# EEM_connector.net
KiCad netlist of a schematic drawn in Altium Designer
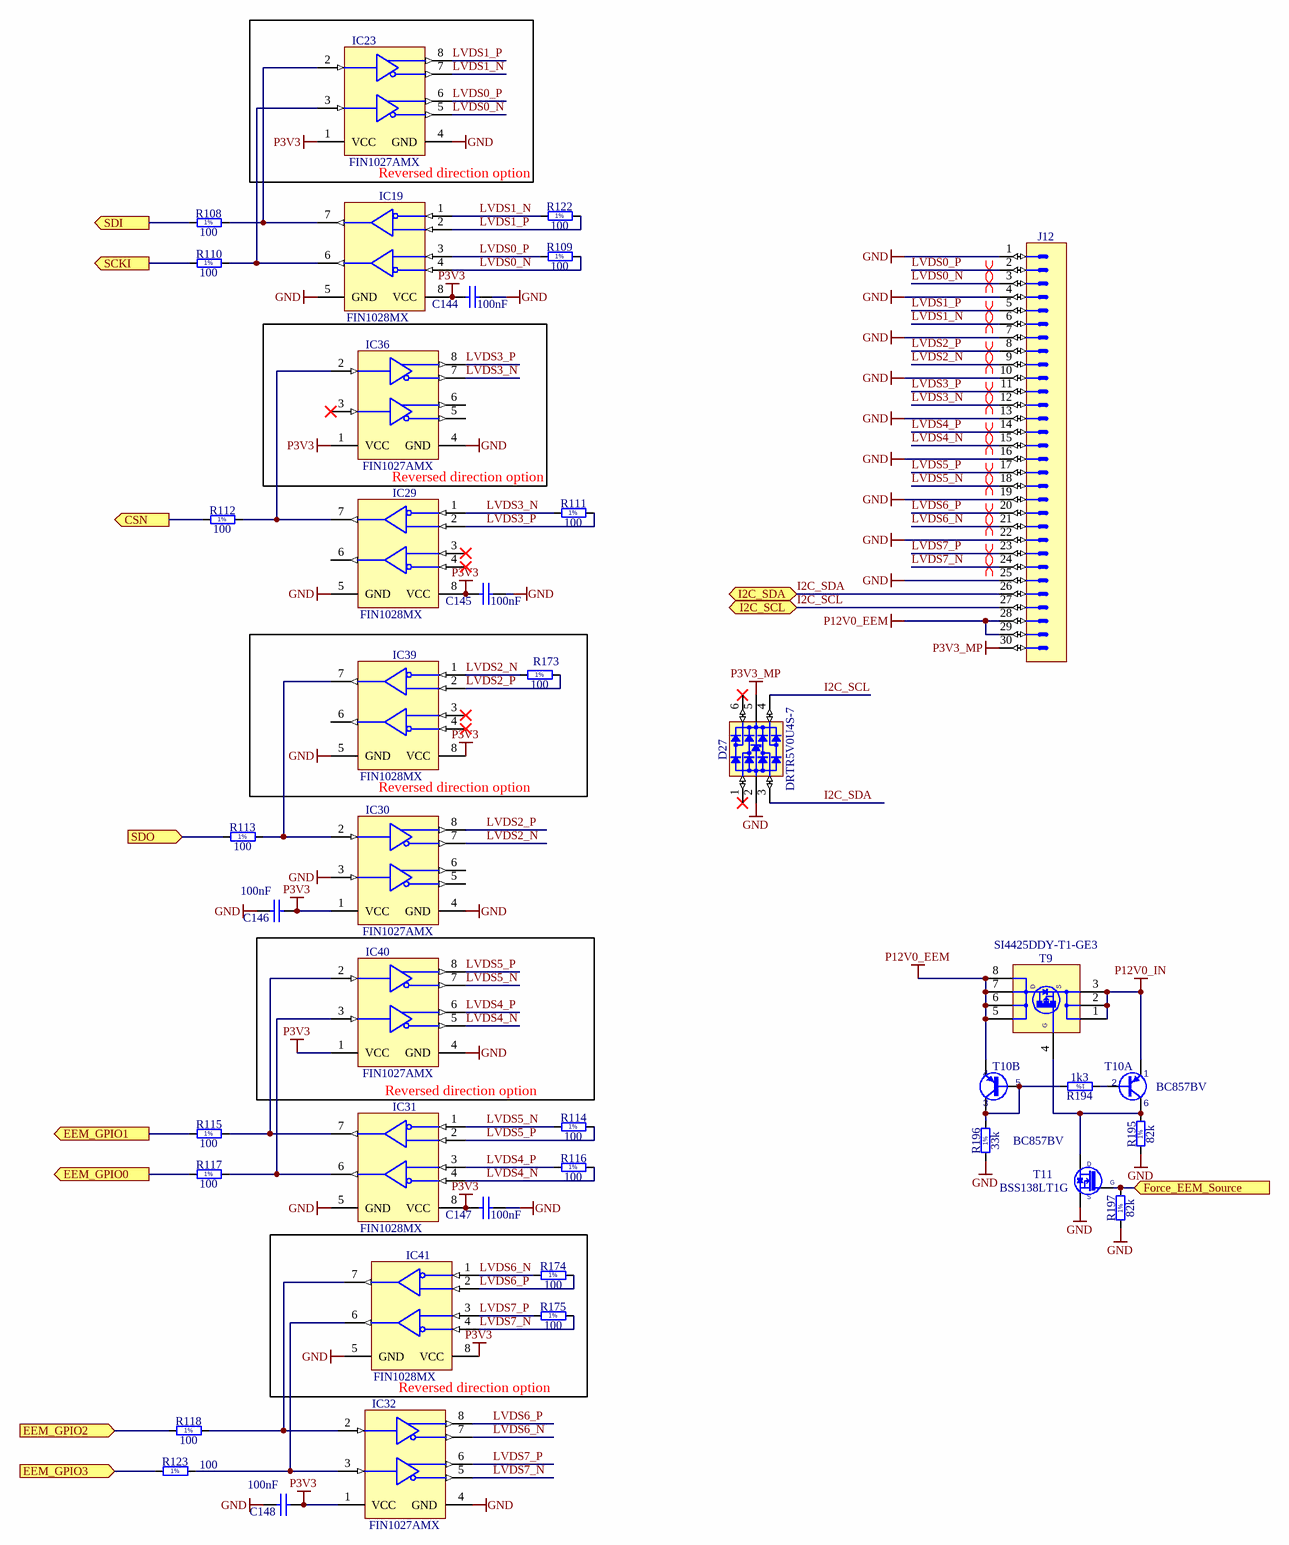
[diagram p0: EEM_connector.SchDoc]

(export (version "E")
  (design (tool "Eeschema 10.0.6"))
  (components
    (comp (ref "C144")
      (value "100nF")
      (footprint "CAPC1005X55N")
      (description "Non-polarised capacitor")
      (fields
        (field (name "PART NUMBER") "CC0402_100NF_16V_10%_X5R")
        (field (name "VOLTAGE") "16V")
        (field (name "AUTHOR") "CERN DEM JLC")
      )
      (libsource (lib "Capacitors") (part "Capacitor - non polarized"))
    )
    (comp (ref "C145")
      (value "100nF")
      (footprint "CAPC1005X55N")
      (description "Non-polarised capacitor")
      (fields
        (field (name "PART NUMBER") "CC0402_100NF_16V_10%_X5R")
        (field (name "VOLTAGE") "16V")
        (field (name "AUTHOR") "CERN DEM JLC")
      )
      (libsource (lib "Capacitors") (part "Capacitor - non polarized"))
    )
    (comp (ref "C146")
      (value "100nF")
      (footprint "CAPC1005X55N")
      (description "Non-polarised capacitor")
      (fields
        (field (name "PART NUMBER") "CC0402_100NF_16V_10%_X5R")
        (field (name "VOLTAGE") "16V")
        (field (name "AUTHOR") "CERN DEM JLC")
      )
      (libsource (lib "Capacitors") (part "Capacitor - non polarized"))
    )
    (comp (ref "C147")
      (value "100nF")
      (footprint "CAPC1005X55N")
      (description "Non-polarised capacitor")
      (fields
        (field (name "PART NUMBER") "CC0402_100NF_16V_10%_X5R")
        (field (name "VOLTAGE") "16V")
        (field (name "AUTHOR") "CERN DEM JLC")
      )
      (libsource (lib "Capacitors") (part "Capacitor - non polarized"))
    )
    (comp (ref "C148")
      (value "100nF")
      (footprint "CAPC1005X55N")
      (description "Non-polarised capacitor")
      (fields
        (field (name "PART NUMBER") "CC0402_100NF_16V_10%_X5R")
        (field (name "VOLTAGE") "16V")
        (field (name "AUTHOR") "CERN DEM JLC")
      )
      (libsource (lib "Capacitors") (part "Capacitor - non polarized"))
    )
    (comp (ref "D27")
      (value "DRTR5V0U4S-7")
      (footprint "SOT65P210X110-6N")
      (description "Integrated Quad Ultra-Low Capacitance ESD Protection")
      (fields (field (name "MANUFACTURER") "DIODES") (field (name "AUTHOR") "GK"))
      (libsource (lib "Diodes") (part "D_TVS_DRTR5V0U4S-7"))
    )
    (comp (ref "IC19")
      (value "FIN1028MX")
      (footprint "SOIC127P600X175-8N")
      (description "3.3V LVDS 2-Bit High-Speed Differential Reciever")
      (fields (field (name "MANUFACTURER") "ON Semiconductor") (field (name "AUTHOR") "GK"))
      (libsource (lib "LIBRARY_SCH") (part "IFC_FIN1028"))
    )
    (comp (ref "IC23")
      (value "FIN1027AMX")
      (footprint "SOIC127P600X175-8N")
      (description "3.3V LVDS, 2-Bit, High-Speed, Differential Driver")
      (fields (field (name "MANUFACTURER") "ON Semiconductor") (field (name "AUTHOR") "GK"))
      (libsource (lib "LIBRARY_SCH") (part "IFC_FIN1027A"))
    )
    (comp (ref "IC29")
      (value "FIN1028MX")
      (footprint "SOIC127P600X175-8N")
      (description "3.3V LVDS 2-Bit High-Speed Differential Reciever")
      (fields (field (name "MANUFACTURER") "ON Semiconductor") (field (name "AUTHOR") "GK"))
      (libsource (lib "LIBRARY_SCH") (part "IFC_FIN1028"))
    )
    (comp (ref "IC30")
      (value "FIN1027AMX")
      (footprint "SOIC127P600X175-8N")
      (description "3.3V LVDS, 2-Bit, High-Speed, Differential Driver")
      (fields (field (name "MANUFACTURER") "ON Semiconductor") (field (name "AUTHOR") "GK"))
      (libsource (lib "LIBRARY_SCH") (part "IFC_FIN1027A"))
    )
    (comp (ref "IC31")
      (value "FIN1028MX")
      (footprint "SOIC127P600X175-8N")
      (description "3.3V LVDS 2-Bit High-Speed Differential Reciever")
      (fields (field (name "MANUFACTURER") "ON Semiconductor") (field (name "AUTHOR") "GK"))
      (libsource (lib "LIBRARY_SCH") (part "IFC_FIN1028"))
    )
    (comp (ref "IC32")
      (value "FIN1027AMX")
      (footprint "SOIC127P600X175-8N")
      (description "3.3V LVDS, 2-Bit, High-Speed, Differential Driver")
      (fields (field (name "MANUFACTURER") "ON Semiconductor") (field (name "AUTHOR") "GK"))
      (libsource (lib "LIBRARY_SCH") (part "IFC_FIN1027A"))
    )
    (comp (ref "IC36")
      (value "FIN1027AMX")
      (footprint "SOIC127P600X175-8N")
      (description "3.3V LVDS, 2-Bit, High-Speed, Differential Driver")
      (fields (field (name "MANUFACTURER") "ON Semiconductor") (field (name "AUTHOR") "GK"))
      (libsource (lib "LIBRARY_SCH") (part "IFC_FIN1027A"))
    )
    (comp (ref "IC39")
      (value "FIN1028MX")
      (footprint "SOIC127P600X175-8N")
      (description "3.3V LVDS 2-Bit High-Speed Differential Reciever")
      (fields (field (name "MANUFACTURER") "ON Semiconductor") (field (name "AUTHOR") "GK"))
      (libsource (lib "LIBRARY_SCH") (part "IFC_FIN1028"))
    )
    (comp (ref "IC40")
      (value "FIN1027AMX")
      (footprint "SOIC127P600X175-8N")
      (description "3.3V LVDS, 2-Bit, High-Speed, Differential Driver")
      (fields (field (name "MANUFACTURER") "ON Semiconductor") (field (name "AUTHOR") "GK"))
      (libsource (lib "LIBRARY_SCH") (part "IFC_FIN1027A"))
    )
    (comp (ref "IC41")
      (value "FIN1028MX")
      (footprint "SOIC127P600X175-8N")
      (description "3.3V LVDS 2-Bit High-Speed Differential Reciever")
      (fields (field (name "MANUFACTURER") "ON Semiconductor") (field (name "AUTHOR") "GK"))
      (libsource (lib "LIBRARY_SCH") (part "IFC_FIN1028"))
    )
    (comp (ref "J12")
      (value "~")
      (footprint "3M_N2530-6002RB")
      (description "Connector 30 Male")
      (fields
        (field (name "PART NUMBER") "3M_N2530-6002RB")
        (field (name "MANUFACTURER") "3M")
        (field (name "AUTHOR") "CERN DEM JLC")
      )
      (libsource (lib "Connectors") (part "Connector 30 Male"))
    )
    (comp (ref "R108")
      (value "100")
      (footprint "RESC1005X40N")
      (description "Resistor - 1%")
      (fields
        (field (name "PART NUMBER") "R0402_100R_1%_0.0625W_100PPM")
        (field (name "POWER") "0.0625W")
        (field (name "AUTHOR") "CERN DEM JLC")
      )
      (libsource (lib "Resistors") (part "Resistor - 1%"))
    )
    (comp (ref "R109")
      (value "100")
      (footprint "RESC1005X40N")
      (description "Resistor - 1%")
      (fields
        (field (name "PART NUMBER") "R0402_100R_1%_0.0625W_100PPM")
        (field (name "POWER") "0.0625W")
        (field (name "AUTHOR") "CERN DEM JLC")
      )
      (libsource (lib "Resistors") (part "Resistor - 1%"))
    )
    (comp (ref "R110")
      (value "100")
      (footprint "RESC1005X40N")
      (description "Resistor - 1%")
      (fields
        (field (name "PART NUMBER") "R0402_100R_1%_0.0625W_100PPM")
        (field (name "POWER") "0.0625W")
        (field (name "AUTHOR") "CERN DEM JLC")
      )
      (libsource (lib "Resistors") (part "Resistor - 1%"))
    )
    (comp (ref "R111")
      (value "100")
      (footprint "RESC1005X40N")
      (description "Resistor - 1%")
      (fields
        (field (name "PART NUMBER") "R0402_100R_1%_0.0625W_100PPM")
        (field (name "POWER") "0.0625W")
        (field (name "AUTHOR") "CERN DEM JLC")
      )
      (libsource (lib "Resistors") (part "Resistor - 1%"))
    )
    (comp (ref "R112")
      (value "100")
      (footprint "RESC1005X40N")
      (description "Resistor - 1%")
      (fields
        (field (name "PART NUMBER") "R0402_100R_1%_0.0625W_100PPM")
        (field (name "POWER") "0.0625W")
        (field (name "AUTHOR") "CERN DEM JLC")
      )
      (libsource (lib "Resistors") (part "Resistor - 1%"))
    )
    (comp (ref "R113")
      (value "100")
      (footprint "RESC1005X40N")
      (description "Resistor - 1%")
      (fields
        (field (name "PART NUMBER") "R0402_100R_1%_0.0625W_100PPM")
        (field (name "POWER") "0.0625W")
        (field (name "AUTHOR") "CERN DEM JLC")
      )
      (libsource (lib "Resistors") (part "Resistor - 1%"))
    )
    (comp (ref "R114")
      (value "100")
      (footprint "RESC1005X40N")
      (description "Resistor - 1%")
      (fields
        (field (name "PART NUMBER") "R0402_100R_1%_0.0625W_100PPM")
        (field (name "POWER") "0.0625W")
        (field (name "AUTHOR") "CERN DEM JLC")
      )
      (libsource (lib "Resistors") (part "Resistor - 1%"))
    )
    (comp (ref "R115")
      (value "100")
      (footprint "RESC1005X40N")
      (description "Resistor - 1%")
      (fields
        (field (name "PART NUMBER") "R0402_100R_1%_0.0625W_100PPM")
        (field (name "POWER") "0.0625W")
        (field (name "AUTHOR") "CERN DEM JLC")
      )
      (libsource (lib "Resistors") (part "Resistor - 1%"))
    )
    (comp (ref "R116")
      (value "100")
      (footprint "RESC1005X40N")
      (description "Resistor - 1%")
      (fields
        (field (name "PART NUMBER") "R0402_100R_1%_0.0625W_100PPM")
        (field (name "POWER") "0.0625W")
        (field (name "AUTHOR") "CERN DEM JLC")
      )
      (libsource (lib "Resistors") (part "Resistor - 1%"))
    )
    (comp (ref "R117")
      (value "100")
      (footprint "RESC1005X40N")
      (description "Resistor - 1%")
      (fields
        (field (name "PART NUMBER") "R0402_100R_1%_0.0625W_100PPM")
        (field (name "POWER") "0.0625W")
        (field (name "AUTHOR") "CERN DEM JLC")
      )
      (libsource (lib "Resistors") (part "Resistor - 1%"))
    )
    (comp (ref "R118")
      (value "100")
      (footprint "RESC1005X40N")
      (description "Resistor - 1%")
      (fields
        (field (name "PART NUMBER") "R0402_100R_1%_0.0625W_100PPM")
        (field (name "POWER") "0.0625W")
        (field (name "AUTHOR") "CERN DEM JLC")
      )
      (libsource (lib "Resistors") (part "Resistor - 1%"))
    )
    (comp (ref "R122")
      (value "100")
      (footprint "RESC1005X40N")
      (description "Resistor - 1%")
      (fields
        (field (name "PART NUMBER") "R0402_100R_1%_0.0625W_100PPM")
        (field (name "POWER") "0.0625W")
        (field (name "AUTHOR") "CERN DEM JLC")
      )
      (libsource (lib "Resistors") (part "Resistor - 1%"))
    )
    (comp (ref "R123")
      (value "100")
      (footprint "RESC1005X40N")
      (description "Resistor - 1%")
      (fields
        (field (name "PART NUMBER") "R0402_100R_1%_0.0625W_100PPM")
        (field (name "POWER") "0.0625W")
        (field (name "AUTHOR") "CERN DEM JLC")
      )
      (libsource (lib "Resistors") (part "Resistor - 1%"))
    )
    (comp (ref "R173")
      (value "100")
      (footprint "RESC1005X40N")
      (description "Resistor - 1%")
      (fields
        (field (name "PART NUMBER") "R0402_100R_1%_0.0625W_100PPM")
        (field (name "POWER") "0.0625W")
        (field (name "AUTHOR") "CERN DEM JLC")
      )
      (libsource (lib "Resistors") (part "Resistor - 1%"))
    )
    (comp (ref "R174")
      (value "100")
      (footprint "RESC1005X40N")
      (description "Resistor - 1%")
      (fields
        (field (name "PART NUMBER") "R0402_100R_1%_0.0625W_100PPM")
        (field (name "POWER") "0.0625W")
        (field (name "AUTHOR") "CERN DEM JLC")
      )
      (libsource (lib "Resistors") (part "Resistor - 1%"))
    )
    (comp (ref "R175")
      (value "100")
      (footprint "RESC1005X40N")
      (description "Resistor - 1%")
      (fields
        (field (name "PART NUMBER") "R0402_100R_1%_0.0625W_100PPM")
        (field (name "POWER") "0.0625W")
        (field (name "AUTHOR") "CERN DEM JLC")
      )
      (libsource (lib "Resistors") (part "Resistor - 1%"))
    )
    (comp (ref "R194")
      (value "1k3")
      (footprint "RESC1608X55N")
      (description "Resistor - 1%")
      (fields
        (field (name "PART NUMBER") "R0603_1K3_1%_0.1W_100PPM")
        (field (name "POWER") "0.1W")
        (field (name "AUTHOR") "CERN DEM JLC")
      )
      (libsource (lib "Resistors") (part "Resistor - 1%"))
    )
    (comp (ref "R195")
      (value "82k")
      (footprint "RESC1608X55N")
      (description "Resistor - 1%")
      (fields
        (field (name "PART NUMBER") "R0603_82K_1%_0.1W_100PPM")
        (field (name "POWER") "0.1W")
        (field (name "AUTHOR") "CERN DEM JLC")
      )
      (libsource (lib "Resistors") (part "Resistor - 1%"))
    )
    (comp (ref "R196")
      (value "33k")
      (footprint "RESC1005X40N")
      (description "Resistor - 1%")
      (fields
        (field (name "PART NUMBER") "R0402_33K_1%_0.0625W_100PPM")
        (field (name "POWER") "0.0625W")
        (field (name "AUTHOR") "CERN DEM JLC")
      )
      (libsource (lib "Resistors") (part "Resistor - 1%"))
    )
    (comp (ref "R197")
      (value "82k")
      (footprint "RESC1608X55N")
      (description "Resistor - 1%")
      (fields
        (field (name "PART NUMBER") "R0603_82K_1%_0.1W_100PPM")
        (field (name "POWER") "0.1W")
        (field (name "AUTHOR") "CERN DEM JLC")
      )
      (libsource (lib "Resistors") (part "Resistor - 1%"))
    )
    (comp (ref "T9")
      (value "SI4425DDY-T1-GE3")
      (footprint "SOIC127P600X175-8N")
      (description "-30V -19.7A P-Channel MOSFET")
      (fields (field (name "MANUFACTURER") "VISHAY SILICONIX") (field (name "AUTHOR") "CERN DEM MR"))
      (libsource (lib "ICs And Semiconductors") (part "SI4425DDY"))
    )
    (comp (ref "T10")
      (value "BC857BV")
      (footprint "SOTFL50P160X60-6N")
      (description "45V, 100mA PNP General Purpose Double Transistor")
      (fields (field (name "MANUFACTURER") "NXP SEMICONDUCTORS") (field (name "AUTHOR") "CERN DEM JLC"))
      (libsource (lib "") (part "BC857BV_1"))
    )
    (comp (ref "T11")
      (value "BSS138LT1G")
      (footprint "SOT95P240X110-3N")
      (description "N-CHANNEL MOSFET WITH DIODE")
      (fields (field (name "MANUFACTURER") "ON SEMICONDUCTOR") (field (name "AUTHOR") "CERN DEM JLC"))
      (libsource (lib "ICs And Semiconductors") (part "N-MOSFET-D 1G 2S 3D"))
    )
  )
  (nets
    (net (code "1") (name "/CSN") (class "Default")
      (node (ref "R112") (pin "1") (pinfunction "1_1") (pintype "passive"))
    )
    (net (code "2") (name "/EEM_GPIO0") (class "Default")
      (node (ref "R117") (pin "1") (pinfunction "1_1") (pintype "passive"))
    )
    (net (code "3") (name "/EEM_GPIO1") (class "Default")
      (node (ref "R115") (pin "1") (pinfunction "1_1") (pintype "passive"))
    )
    (net (code "4") (name "/EEM_GPIO2") (class "Default")
      (node (ref "R118") (pin "1") (pinfunction "1_1") (pintype "passive"))
    )
    (net (code "5") (name "/EEM_GPIO3") (class "Default")
      (node (ref "R123") (pin "1") (pinfunction "1_1") (pintype "passive"))
    )
    (net (code "6") (name "/Force_EEM_Source") (class "Default")
      (node (ref "R197") (pin "2") (pinfunction "2_2") (pintype "passive"))
      (node (ref "T11") (pin "1") (pinfunction "G_1") (pintype "passive"))
    )
    (net (code "7") (name "/I2C_SCL") (class "Default")
      (node (ref "D27") (pin "4") (pinfunction "I/O3_4") (pintype "bidirectional"))
      (node (ref "J12") (pin "27") (pinfunction "27_27") (pintype "bidirectional"))
    )
    (net (code "8") (name "/I2C_SDA") (class "Default")
      (node (ref "D27") (pin "3") (pinfunction "I/O2_3") (pintype "bidirectional"))
      (node (ref "J12") (pin "26") (pinfunction "26_26") (pintype "bidirectional"))
    )
    (net (code "9") (name "/LVDS0_N") (class "Default")
      (node (ref "IC19") (pin "4") (pinfunction "RIN2-_4") (pintype "input"))
      (node (ref "IC23") (pin "5") (pinfunction "DOUT-_5") (pintype "output"))
      (node (ref "J12") (pin "3") (pinfunction "3_3") (pintype "bidirectional"))
      (node (ref "R109") (pin "2") (pinfunction "2_2") (pintype "passive"))
    )
    (net (code "10") (name "/LVDS0_P") (class "Default")
      (node (ref "IC19") (pin "3") (pinfunction "RIN2+_3") (pintype "input"))
      (node (ref "IC23") (pin "6") (pinfunction "DOUT+_6") (pintype "output"))
      (node (ref "J12") (pin "2") (pinfunction "2_2") (pintype "bidirectional"))
      (node (ref "R109") (pin "1") (pinfunction "1_1") (pintype "passive"))
    )
    (net (code "11") (name "/LVDS1_N") (class "Default")
      (node (ref "IC19") (pin "1") (pinfunction "RIN1-_1") (pintype "input"))
      (node (ref "IC23") (pin "7") (pinfunction "DOUT-_7") (pintype "output"))
      (node (ref "J12") (pin "6") (pinfunction "6_6") (pintype "bidirectional"))
      (node (ref "R122") (pin "1") (pinfunction "1_1") (pintype "passive"))
    )
    (net (code "12") (name "/LVDS1_P") (class "Default")
      (node (ref "IC19") (pin "2") (pinfunction "RIN1+_2") (pintype "input"))
      (node (ref "IC23") (pin "8") (pinfunction "DOUT+_8") (pintype "output"))
      (node (ref "J12") (pin "5") (pinfunction "5_5") (pintype "bidirectional"))
      (node (ref "R122") (pin "2") (pinfunction "2_2") (pintype "passive"))
    )
    (net (code "13") (name "/LVDS2_N") (class "Default")
      (node (ref "IC30") (pin "7") (pinfunction "DOUT-_7") (pintype "output"))
      (node (ref "IC39") (pin "1") (pinfunction "RIN1-_1") (pintype "input"))
      (node (ref "J12") (pin "9") (pinfunction "9_9") (pintype "bidirectional"))
      (node (ref "R173") (pin "1") (pinfunction "1_1") (pintype "passive"))
    )
    (net (code "14") (name "/LVDS2_P") (class "Default")
      (node (ref "IC30") (pin "8") (pinfunction "DOUT+_8") (pintype "output"))
      (node (ref "IC39") (pin "2") (pinfunction "RIN1+_2") (pintype "input"))
      (node (ref "J12") (pin "8") (pinfunction "8_8") (pintype "bidirectional"))
      (node (ref "R173") (pin "2") (pinfunction "2_2") (pintype "passive"))
    )
    (net (code "15") (name "/LVDS3_N") (class "Default")
      (node (ref "IC29") (pin "1") (pinfunction "RIN1-_1") (pintype "input"))
      (node (ref "IC36") (pin "7") (pinfunction "DOUT-_7") (pintype "output"))
      (node (ref "J12") (pin "12") (pinfunction "12_12") (pintype "bidirectional"))
      (node (ref "R111") (pin "1") (pinfunction "1_1") (pintype "passive"))
    )
    (net (code "16") (name "/LVDS3_P") (class "Default")
      (node (ref "IC29") (pin "2") (pinfunction "RIN1+_2") (pintype "input"))
      (node (ref "IC36") (pin "8") (pinfunction "DOUT+_8") (pintype "output"))
      (node (ref "J12") (pin "11") (pinfunction "11_11") (pintype "bidirectional"))
      (node (ref "R111") (pin "2") (pinfunction "2_2") (pintype "passive"))
    )
    (net (code "17") (name "/LVDS4_N") (class "Default")
      (node (ref "IC31") (pin "4") (pinfunction "RIN2-_4") (pintype "input"))
      (node (ref "IC40") (pin "5") (pinfunction "DOUT-_5") (pintype "output"))
      (node (ref "J12") (pin "15") (pinfunction "15_15") (pintype "bidirectional"))
      (node (ref "R116") (pin "2") (pinfunction "2_2") (pintype "passive"))
    )
    (net (code "18") (name "/LVDS4_P") (class "Default")
      (node (ref "IC31") (pin "3") (pinfunction "RIN2+_3") (pintype "input"))
      (node (ref "IC40") (pin "6") (pinfunction "DOUT+_6") (pintype "output"))
      (node (ref "J12") (pin "14") (pinfunction "14_14") (pintype "bidirectional"))
      (node (ref "R116") (pin "1") (pinfunction "1_1") (pintype "passive"))
    )
    (net (code "19") (name "/LVDS5_N") (class "Default")
      (node (ref "IC31") (pin "1") (pinfunction "RIN1-_1") (pintype "input"))
      (node (ref "IC40") (pin "7") (pinfunction "DOUT-_7") (pintype "output"))
      (node (ref "J12") (pin "18") (pinfunction "18_18") (pintype "bidirectional"))
      (node (ref "R114") (pin "1") (pinfunction "1_1") (pintype "passive"))
    )
    (net (code "20") (name "/LVDS5_P") (class "Default")
      (node (ref "IC31") (pin "2") (pinfunction "RIN1+_2") (pintype "input"))
      (node (ref "IC40") (pin "8") (pinfunction "DOUT+_8") (pintype "output"))
      (node (ref "J12") (pin "17") (pinfunction "17_17") (pintype "bidirectional"))
      (node (ref "R114") (pin "2") (pinfunction "2_2") (pintype "passive"))
    )
    (net (code "21") (name "/LVDS6_N") (class "Default")
      (node (ref "IC32") (pin "7") (pinfunction "DOUT-_7") (pintype "output"))
      (node (ref "IC41") (pin "1") (pinfunction "RIN1-_1") (pintype "input"))
      (node (ref "J12") (pin "21") (pinfunction "21_21") (pintype "bidirectional"))
      (node (ref "R174") (pin "1") (pinfunction "1_1") (pintype "passive"))
    )
    (net (code "22") (name "/LVDS6_P") (class "Default")
      (node (ref "IC32") (pin "8") (pinfunction "DOUT+_8") (pintype "output"))
      (node (ref "IC41") (pin "2") (pinfunction "RIN1+_2") (pintype "input"))
      (node (ref "J12") (pin "20") (pinfunction "20_20") (pintype "bidirectional"))
      (node (ref "R174") (pin "2") (pinfunction "2_2") (pintype "passive"))
    )
    (net (code "23") (name "/LVDS7_N") (class "Default")
      (node (ref "IC32") (pin "5") (pinfunction "DOUT-_5") (pintype "output"))
      (node (ref "IC41") (pin "4") (pinfunction "RIN2-_4") (pintype "input"))
      (node (ref "J12") (pin "24") (pinfunction "24_24") (pintype "bidirectional"))
      (node (ref "R175") (pin "2") (pinfunction "2_2") (pintype "passive"))
    )
    (net (code "24") (name "/LVDS7_P") (class "Default")
      (node (ref "IC32") (pin "6") (pinfunction "DOUT+_6") (pintype "output"))
      (node (ref "IC41") (pin "3") (pinfunction "RIN2+_3") (pintype "input"))
      (node (ref "J12") (pin "23") (pinfunction "23_23") (pintype "bidirectional"))
      (node (ref "R175") (pin "1") (pinfunction "1_1") (pintype "passive"))
    )
    (net (code "25") (name "/SCKI") (class "Default")
      (node (ref "R110") (pin "1") (pinfunction "1_1") (pintype "passive"))
    )
    (net (code "26") (name "/SDI") (class "Default")
      (node (ref "R108") (pin "1") (pinfunction "1_1") (pintype "passive"))
    )
    (net (code "27") (name "/SDO") (class "Default")
      (node (ref "R113") (pin "1") (pinfunction "1_1") (pintype "passive"))
    )
    (net (code "28") (name "GND") (class "Default")
      (node (ref "C144") (pin "1") (pinfunction "1_1") (pintype "passive"))
      (node (ref "C145") (pin "1") (pinfunction "1_1") (pintype "passive"))
      (node (ref "C146") (pin "1") (pinfunction "1_1") (pintype "passive"))
      (node (ref "C147") (pin "1") (pinfunction "1_1") (pintype "passive"))
      (node (ref "C148") (pin "1") (pinfunction "1_1") (pintype "passive"))
      (node (ref "D27") (pin "2") (pinfunction "GND_2") (pintype "power_in"))
      (node (ref "IC19") (pin "5") (pinfunction "GND_5") (pintype "power_in"))
      (node (ref "IC23") (pin "4") (pinfunction "GND_4") (pintype "power_in"))
      (node (ref "IC29") (pin "5") (pinfunction "GND_5") (pintype "power_in"))
      (node (ref "IC30") (pin "3") (pinfunction "DIN2RIN-_3") (pintype "input"))
      (node (ref "IC30") (pin "4") (pinfunction "GND_4") (pintype "power_in"))
      (node (ref "IC31") (pin "5") (pinfunction "GND_5") (pintype "power_in"))
      (node (ref "IC32") (pin "4") (pinfunction "GND_4") (pintype "power_in"))
      (node (ref "IC36") (pin "4") (pinfunction "GND_4") (pintype "power_in"))
      (node (ref "IC39") (pin "5") (pinfunction "GND_5") (pintype "power_in"))
      (node (ref "IC40") (pin "4") (pinfunction "GND_4") (pintype "power_in"))
      (node (ref "IC41") (pin "5") (pinfunction "GND_5") (pintype "power_in"))
      (node (ref "J12") (pin "1") (pinfunction "1_1") (pintype "bidirectional"))
      (node (ref "J12") (pin "10") (pinfunction "10_10") (pintype "bidirectional"))
      (node (ref "J12") (pin "13") (pinfunction "13_13") (pintype "bidirectional"))
      (node (ref "J12") (pin "16") (pinfunction "16_16") (pintype "bidirectional"))
      (node (ref "J12") (pin "19") (pinfunction "19_19") (pintype "bidirectional"))
      (node (ref "J12") (pin "22") (pinfunction "22_22") (pintype "bidirectional"))
      (node (ref "J12") (pin "25") (pinfunction "25_25") (pintype "bidirectional"))
      (node (ref "J12") (pin "4") (pinfunction "4_4") (pintype "bidirectional"))
      (node (ref "J12") (pin "7") (pinfunction "7_7") (pintype "bidirectional"))
      (node (ref "R195") (pin "1") (pinfunction "1_1") (pintype "passive"))
      (node (ref "R196") (pin "1") (pinfunction "1_1") (pintype "passive"))
      (node (ref "R197") (pin "1") (pinfunction "1_1") (pintype "passive"))
      (node (ref "T11") (pin "2") (pinfunction "S_2") (pintype "passive"))
    )
    (net (code "29") (name "Net-(IC19-ROUT1)") (class "Default")
      (node (ref "IC19") (pin "7") (pinfunction "ROUT1_7") (pintype "output"))
      (node (ref "IC23") (pin "2") (pinfunction "DIN1_2") (pintype "input"))
      (node (ref "R108") (pin "2") (pinfunction "2_2") (pintype "passive"))
    )
    (net (code "30") (name "Net-(IC19-ROUT2)") (class "Default")
      (node (ref "IC19") (pin "6") (pinfunction "ROUT2_6") (pintype "output"))
      (node (ref "IC23") (pin "3") (pinfunction "DIN2RIN-_3") (pintype "input"))
      (node (ref "R110") (pin "2") (pinfunction "2_2") (pintype "passive"))
    )
    (net (code "31") (name "Net-(IC29-ROUT1)") (class "Default")
      (node (ref "IC29") (pin "7") (pinfunction "ROUT1_7") (pintype "output"))
      (node (ref "IC36") (pin "2") (pinfunction "DIN1_2") (pintype "input"))
      (node (ref "R112") (pin "2") (pinfunction "2_2") (pintype "passive"))
    )
    (net (code "32") (name "Net-(IC30-DIN1)") (class "Default")
      (node (ref "IC30") (pin "2") (pinfunction "DIN1_2") (pintype "input"))
      (node (ref "IC39") (pin "7") (pinfunction "ROUT1_7") (pintype "output"))
      (node (ref "R113") (pin "2") (pinfunction "2_2") (pintype "passive"))
    )
    (net (code "33") (name "Net-(IC31-ROUT1)") (class "Default")
      (node (ref "IC31") (pin "7") (pinfunction "ROUT1_7") (pintype "output"))
      (node (ref "IC40") (pin "2") (pinfunction "DIN1_2") (pintype "input"))
      (node (ref "R115") (pin "2") (pinfunction "2_2") (pintype "passive"))
    )
    (net (code "34") (name "Net-(IC31-ROUT2)") (class "Default")
      (node (ref "IC31") (pin "6") (pinfunction "ROUT2_6") (pintype "output"))
      (node (ref "IC40") (pin "3") (pinfunction "DIN2RIN-_3") (pintype "input"))
      (node (ref "R117") (pin "2") (pinfunction "2_2") (pintype "passive"))
    )
    (net (code "35") (name "Net-(IC32-DIN1)") (class "Default")
      (node (ref "IC32") (pin "2") (pinfunction "DIN1_2") (pintype "input"))
      (node (ref "IC41") (pin "7") (pinfunction "ROUT1_7") (pintype "output"))
      (node (ref "R118") (pin "2") (pinfunction "2_2") (pintype "passive"))
    )
    (net (code "36") (name "Net-(IC32-DIN2RIN-)") (class "Default")
      (node (ref "IC32") (pin "3") (pinfunction "DIN2RIN-_3") (pintype "input"))
      (node (ref "IC41") (pin "6") (pinfunction "ROUT2_6") (pintype "output"))
      (node (ref "R123") (pin "2") (pinfunction "2_2") (pintype "passive"))
    )
    (net (code "37") (name "Net-(T10A-B)") (class "Default")
      (node (ref "R194") (pin "1") (pinfunction "1_1") (pintype "passive"))
      (node (ref "T10") (pin "2") (pinfunction "B_2") (pintype "passive"))
    )
    (net (code "38") (name "Net-(T10A-C)") (class "Default")
      (node (ref "R195") (pin "2") (pinfunction "2_2") (pintype "passive"))
      (node (ref "T10") (pin "6") (pinfunction "C_6") (pintype "passive"))
      (node (ref "T11") (pin "3") (pinfunction "D_3") (pintype "passive"))
      (node (ref "T9") (pin "4") (pinfunction "S_4") (pintype "passive"))
    )
    (net (code "39") (name "Net-(T10B-B)") (class "Default")
      (node (ref "R194") (pin "2") (pinfunction "2_2") (pintype "passive"))
      (node (ref "R196") (pin "2") (pinfunction "2_2") (pintype "passive"))
      (node (ref "T10") (pin "3") (pinfunction "C_3") (pintype "passive"))
      (node (ref "T10") (pin "5") (pinfunction "B_5") (pintype "passive"))
    )
    (net (code "40") (name "P3V3") (class "Default")
      (node (ref "C144") (pin "2") (pinfunction "2_2") (pintype "passive"))
      (node (ref "C145") (pin "2") (pinfunction "2_2") (pintype "passive"))
      (node (ref "C146") (pin "2") (pinfunction "2_2") (pintype "passive"))
      (node (ref "C147") (pin "2") (pinfunction "2_2") (pintype "passive"))
      (node (ref "C148") (pin "2") (pinfunction "2_2") (pintype "passive"))
      (node (ref "IC19") (pin "8") (pinfunction "VCC_8") (pintype "power_in"))
      (node (ref "IC23") (pin "1") (pinfunction "VCC_1") (pintype "power_in"))
      (node (ref "IC29") (pin "8") (pinfunction "VCC_8") (pintype "power_in"))
      (node (ref "IC30") (pin "1") (pinfunction "VCC_1") (pintype "power_in"))
      (node (ref "IC31") (pin "8") (pinfunction "VCC_8") (pintype "power_in"))
      (node (ref "IC32") (pin "1") (pinfunction "VCC_1") (pintype "power_in"))
      (node (ref "IC36") (pin "1") (pinfunction "VCC_1") (pintype "power_in"))
      (node (ref "IC39") (pin "8") (pinfunction "VCC_8") (pintype "power_in"))
      (node (ref "IC40") (pin "1") (pinfunction "VCC_1") (pintype "power_in"))
      (node (ref "IC41") (pin "8") (pinfunction "VCC_8") (pintype "power_in"))
    )
    (net (code "41") (name "P3V3_MP") (class "Default")
      (node (ref "D27") (pin "5") (pinfunction "VBUS_5") (pintype "power_in"))
      (node (ref "J12") (pin "30") (pinfunction "30_30") (pintype "bidirectional"))
    )
    (net (code "42") (name "P12V0_EEM") (class "Default")
      (node (ref "J12") (pin "28") (pinfunction "28_28") (pintype "bidirectional"))
      (node (ref "J12") (pin "29") (pinfunction "29_29") (pintype "bidirectional"))
      (node (ref "T10") (pin "4") (pinfunction "E_4") (pintype "passive"))
      (node (ref "T9") (pin "5") (pinfunction "D_5") (pintype "passive"))
      (node (ref "T9") (pin "6") (pinfunction "D_6") (pintype "passive"))
      (node (ref "T9") (pin "7") (pinfunction "D_7") (pintype "passive"))
      (node (ref "T9") (pin "8") (pinfunction "D_8") (pintype "passive"))
    )
    (net (code "43") (name "P12V0_IN") (class "Default")
      (node (ref "T10") (pin "1") (pinfunction "E_1") (pintype "passive"))
      (node (ref "T9") (pin "1") (pinfunction "S_1") (pintype "passive"))
      (node (ref "T9") (pin "2") (pinfunction "S_2") (pintype "passive"))
      (node (ref "T9") (pin "3") (pinfunction "S_3") (pintype "passive"))
    )
    (net (code "44") (name "unconnected-(D27-I{slash}O1-Pad1)") (class "Default")
      (node (ref "D27") (pin "1") (pinfunction "I/O1_1") (pintype "bidirectional+no_connect"))
    )
    (net (code "45") (name "unconnected-(D27-I{slash}O4-Pad6)") (class "Default")
      (node (ref "D27") (pin "6") (pinfunction "I/O4_6") (pintype "bidirectional+no_connect"))
    )
    (net (code "46") (name "unconnected-(IC29-RIN2+-Pad3)") (class "Default")
      (node (ref "IC29") (pin "3") (pinfunction "RIN2+_3") (pintype "input+no_connect"))
    )
    (net (code "47") (name "unconnected-(IC29-RIN2--Pad4)") (class "Default")
      (node (ref "IC29") (pin "4") (pinfunction "RIN2-_4") (pintype "input+no_connect"))
    )
    (net (code "48") (name "unconnected-(IC29-ROUT2-Pad6)") (class "Default")
      (node (ref "IC29") (pin "6") (pinfunction "ROUT2_6") (pintype "output"))
    )
    (net (code "49") (name "unconnected-(IC30-DOUT+-Pad6)") (class "Default")
      (node (ref "IC30") (pin "6") (pinfunction "DOUT+_6") (pintype "output"))
    )
    (net (code "50") (name "unconnected-(IC30-DOUT--Pad5)") (class "Default")
      (node (ref "IC30") (pin "5") (pinfunction "DOUT-_5") (pintype "output"))
    )
    (net (code "51") (name "unconnected-(IC36-DIN2RIN--Pad3)") (class "Default")
      (node (ref "IC36") (pin "3") (pinfunction "DIN2RIN-_3") (pintype "input+no_connect"))
    )
    (net (code "52") (name "unconnected-(IC36-DOUT+-Pad6)") (class "Default")
      (node (ref "IC36") (pin "6") (pinfunction "DOUT+_6") (pintype "output"))
    )
    (net (code "53") (name "unconnected-(IC36-DOUT--Pad5)") (class "Default")
      (node (ref "IC36") (pin "5") (pinfunction "DOUT-_5") (pintype "output"))
    )
    (net (code "54") (name "unconnected-(IC39-RIN2+-Pad3)") (class "Default")
      (node (ref "IC39") (pin "3") (pinfunction "RIN2+_3") (pintype "input+no_connect"))
    )
    (net (code "55") (name "unconnected-(IC39-RIN2--Pad4)") (class "Default")
      (node (ref "IC39") (pin "4") (pinfunction "RIN2-_4") (pintype "input+no_connect"))
    )
    (net (code "56") (name "unconnected-(IC39-ROUT2-Pad6)") (class "Default")
      (node (ref "IC39") (pin "6") (pinfunction "ROUT2_6") (pintype "output"))
    )
  )
)
